# 006.net
KiCad netlist of a schematic drawn in EAGLE
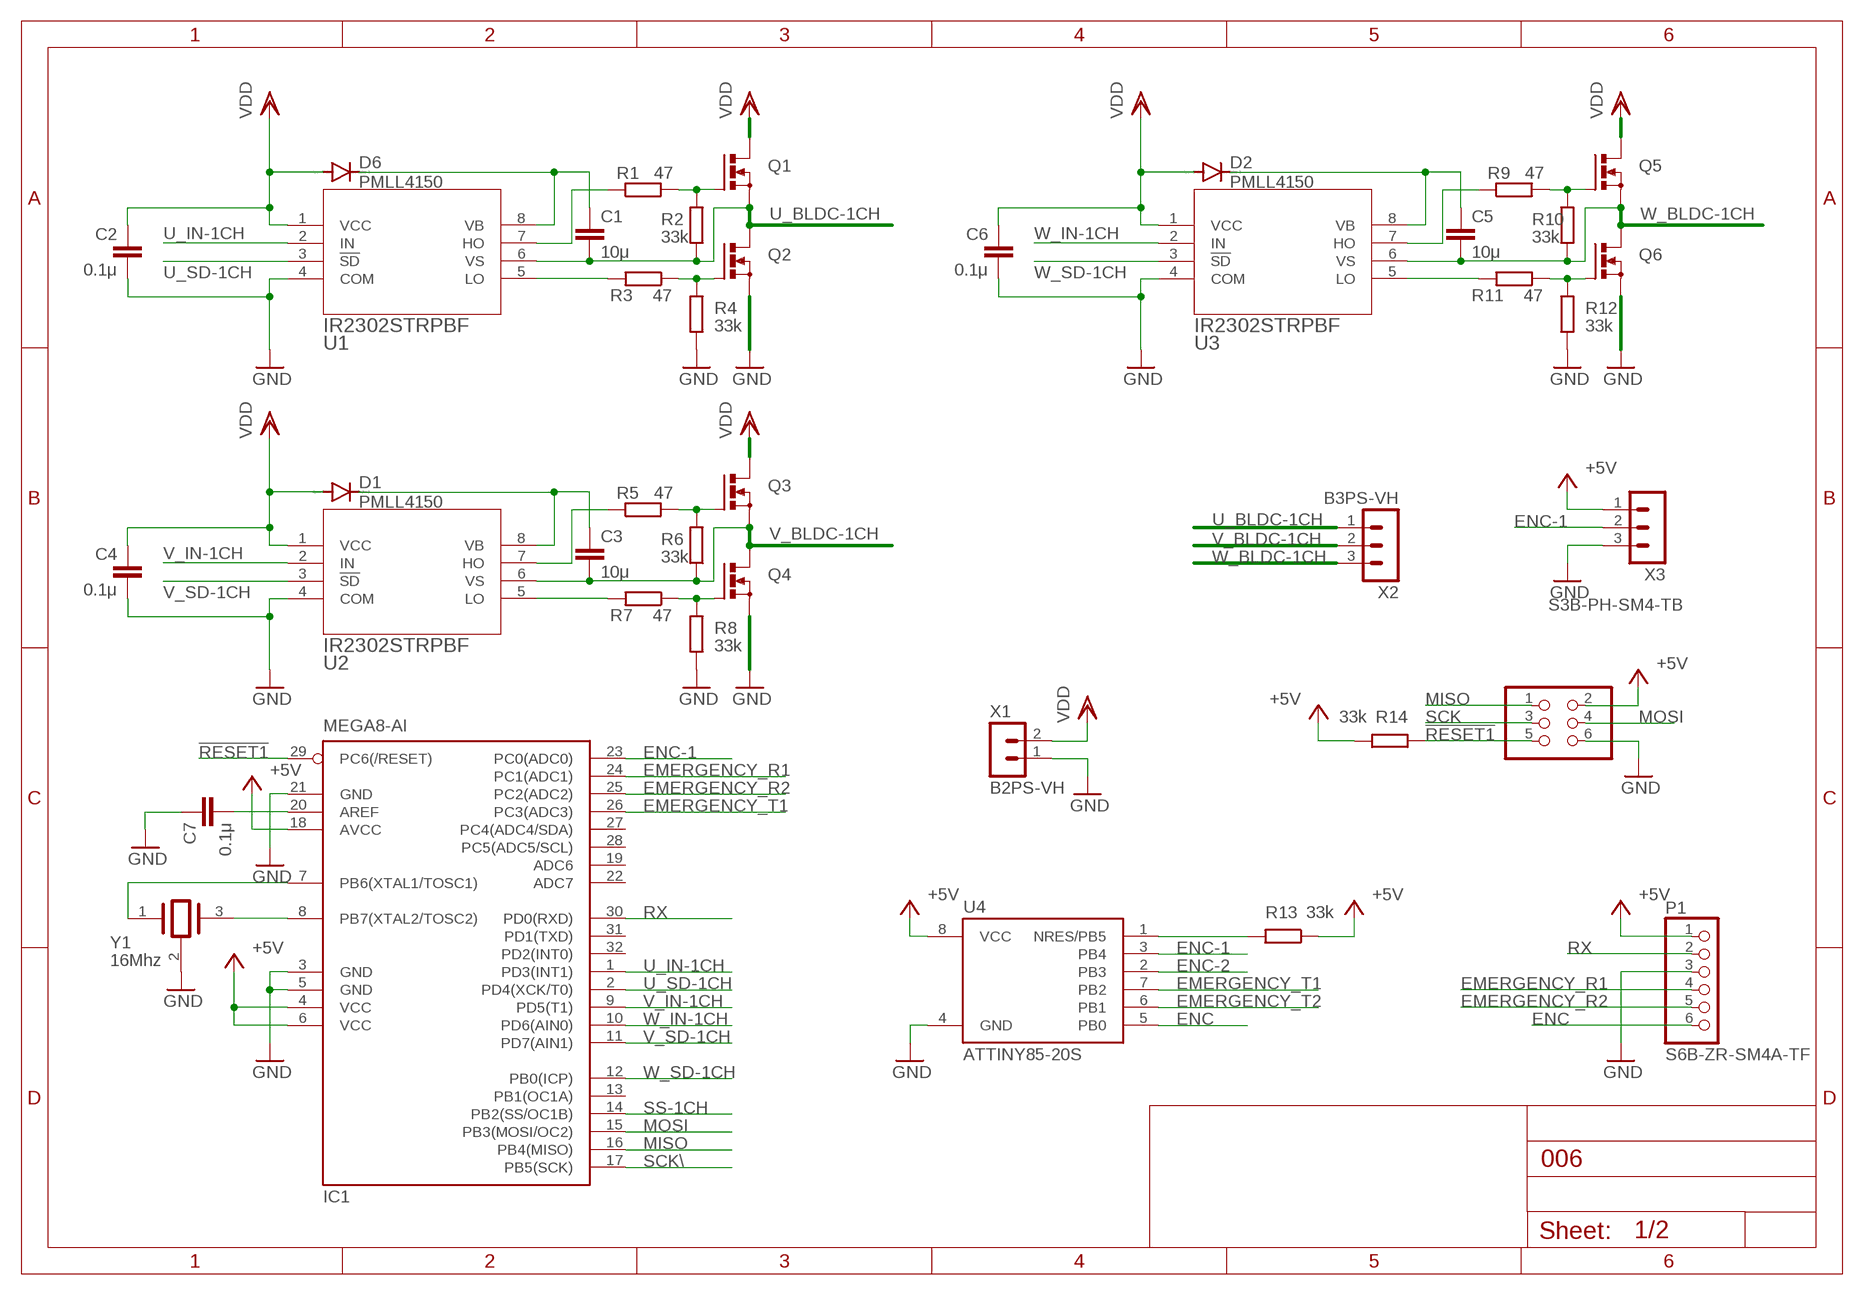
[diagram p0: schematic, sheet 1]
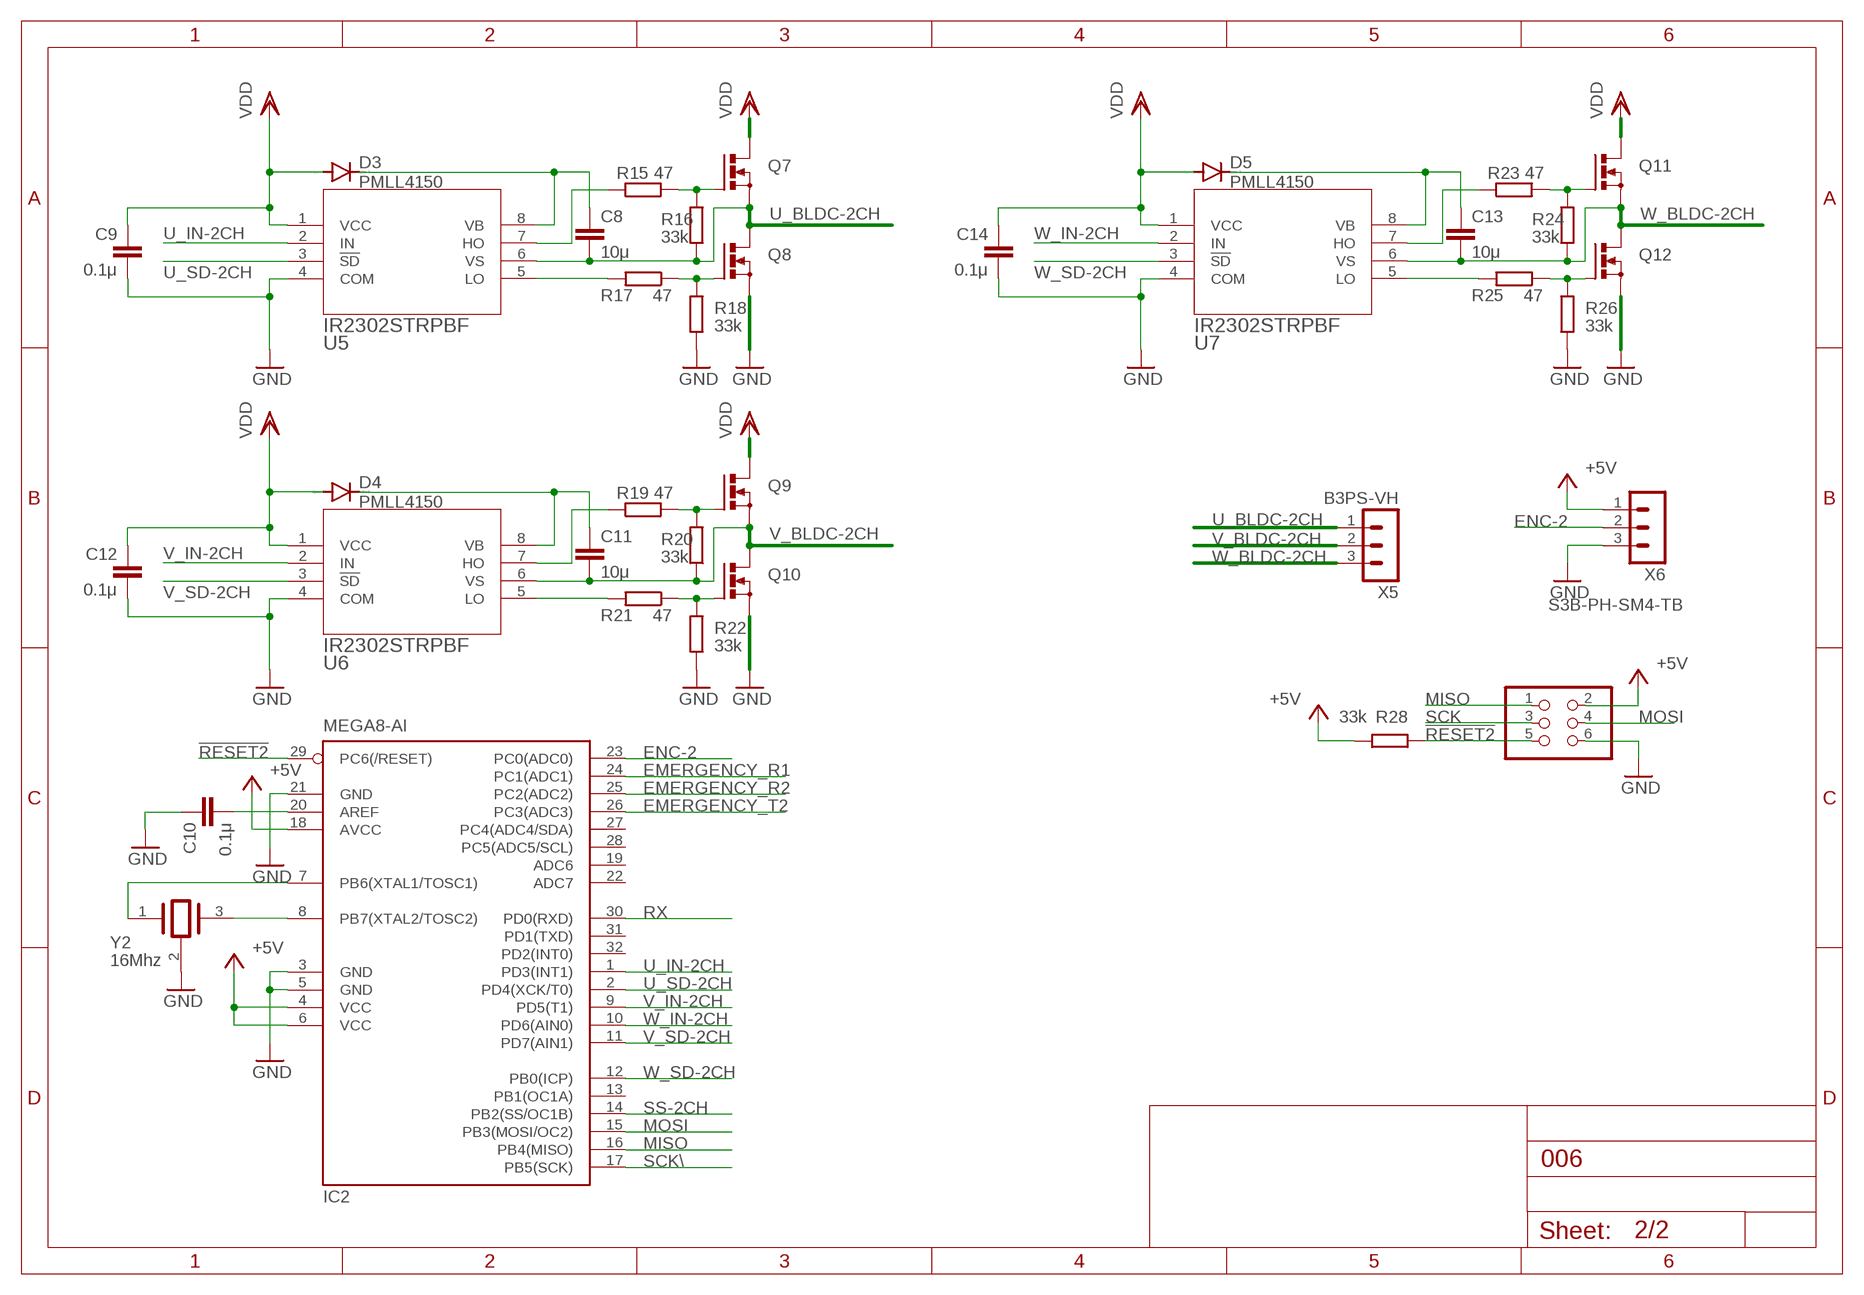
[diagram p1: schematic, sheet 2]

(export (version "E")
  (design (tool "Eeschema 10.0.6"))
  (components
    (comp (ref "C8")
      (value "10μ")
      (footprint "eagle-import:C1608")
      (libsource (lib "eagle-import") (part "C-EUC1608"))
    )
    (comp (ref "C9")
      (value "0.1μ")
      (footprint "eagle-import:C1608")
      (libsource (lib "eagle-import") (part "C-EUC1608"))
    )
    (comp (ref "C10")
      (value "0.1μ")
      (footprint "eagle-import:C1608")
      (libsource (lib "eagle-import") (part "C-EUC1608"))
    )
    (comp (ref "C11")
      (value "10μ")
      (footprint "eagle-import:C1608")
      (libsource (lib "eagle-import") (part "C-EUC1608"))
    )
    (comp (ref "C12")
      (value "0.1μ")
      (footprint "eagle-import:C1608")
      (libsource (lib "eagle-import") (part "C-EUC1608"))
    )
    (comp (ref "C13")
      (value "10μ")
      (footprint "eagle-import:C1608")
      (libsource (lib "eagle-import") (part "C-EUC1608"))
    )
    (comp (ref "C14")
      (value "0.1μ")
      (footprint "eagle-import:C1608")
      (libsource (lib "eagle-import") (part "C-EUC1608"))
    )
    (comp (ref "D3")
      (value "PMLL4150")
      (footprint "eagle-import:SOD80C")
      (libsource (lib "eagle-import") (part "PMLL4150"))
    )
    (comp (ref "D4")
      (value "PMLL4150")
      (footprint "eagle-import:SOD80C")
      (libsource (lib "eagle-import") (part "PMLL4150"))
    )
    (comp (ref "D5")
      (value "PMLL4150")
      (footprint "eagle-import:SOD80C")
      (libsource (lib "eagle-import") (part "PMLL4150"))
    )
    (comp (ref "IC2")
      (value "MEGA8-AI")
      (footprint "eagle-import:TQFP32-08")
      (fields (field (name "MPN") "ATMEGA8-16AU"))
      (libsource (lib "eagle-import") (part "MEGA8-AI"))
    )
    (comp (ref "JP2")
      (value "PINHD-2X3")
      (footprint "eagle-import:2X03")
      (libsource (lib "eagle-import") (part "PINHD-2X3"))
    )
    (comp (ref "Q7")
      (value "N-MOSFET-SO8S")
      (footprint "eagle-import:SO-08")
      (libsource (lib "eagle-import") (part "N-MOSFET-SO8S"))
    )
    (comp (ref "Q8")
      (value "N-MOSFET-SO8S")
      (footprint "eagle-import:SO-08")
      (libsource (lib "eagle-import") (part "N-MOSFET-SO8S"))
    )
    (comp (ref "Q9")
      (value "N-MOSFET-SO8S")
      (footprint "eagle-import:SO-08")
      (libsource (lib "eagle-import") (part "N-MOSFET-SO8S"))
    )
    (comp (ref "Q10")
      (value "N-MOSFET-SO8S")
      (footprint "eagle-import:SO-08")
      (libsource (lib "eagle-import") (part "N-MOSFET-SO8S"))
    )
    (comp (ref "Q11")
      (value "N-MOSFET-SO8S")
      (footprint "eagle-import:SO-08")
      (libsource (lib "eagle-import") (part "N-MOSFET-SO8S"))
    )
    (comp (ref "Q12")
      (value "N-MOSFET-SO8S")
      (footprint "eagle-import:SO-08")
      (libsource (lib "eagle-import") (part "N-MOSFET-SO8S"))
    )
    (comp (ref "R15")
      (value "47")
      (footprint "eagle-import:R0603")
      (libsource (lib "eagle-import") (part "R-EU_R0603"))
    )
    (comp (ref "R16")
      (value "33k")
      (footprint "eagle-import:R0603")
      (libsource (lib "eagle-import") (part "R-EU_R0603"))
    )
    (comp (ref "R17")
      (value "47")
      (footprint "eagle-import:R0603")
      (libsource (lib "eagle-import") (part "R-EU_R0603"))
    )
    (comp (ref "R18")
      (value "33k")
      (footprint "eagle-import:R0603")
      (libsource (lib "eagle-import") (part "R-EU_R0603"))
    )
    (comp (ref "R19")
      (value "47")
      (footprint "eagle-import:R0603")
      (libsource (lib "eagle-import") (part "R-EU_R0603"))
    )
    (comp (ref "R20")
      (value "33k")
      (footprint "eagle-import:R0603")
      (libsource (lib "eagle-import") (part "R-EU_R0603"))
    )
    (comp (ref "R21")
      (value "47")
      (footprint "eagle-import:R0603")
      (libsource (lib "eagle-import") (part "R-EU_R0603"))
    )
    (comp (ref "R22")
      (value "33k")
      (footprint "eagle-import:R0603")
      (libsource (lib "eagle-import") (part "R-EU_R0603"))
    )
    (comp (ref "R23")
      (value "47")
      (footprint "eagle-import:R0603")
      (libsource (lib "eagle-import") (part "R-EU_R0603"))
    )
    (comp (ref "R24")
      (value "33k")
      (footprint "eagle-import:R0603")
      (libsource (lib "eagle-import") (part "R-EU_R0603"))
    )
    (comp (ref "R25")
      (value "47")
      (footprint "eagle-import:R0603")
      (libsource (lib "eagle-import") (part "R-EU_R0603"))
    )
    (comp (ref "R26")
      (value "33k")
      (footprint "eagle-import:R0603")
      (libsource (lib "eagle-import") (part "R-EU_R0603"))
    )
    (comp (ref "R28")
      (value "33k")
      (footprint "eagle-import:R0603")
      (libsource (lib "eagle-import") (part "R-EU_R0603"))
    )
    (comp (ref "U5")
      (value "IR2302STRPBF")
      (footprint "eagle-import:PG-DSO-8-910_INF")
      (fields (field (name "COPYRIGHT") "Copyright (C) 2018 Accelerated Designs. All rights reserved"))
      (libsource (lib "eagle-import") (part "IR2302STRPBF"))
    )
    (comp (ref "U6")
      (value "IR2302STRPBF")
      (footprint "eagle-import:PG-DSO-8-910_INF")
      (fields (field (name "COPYRIGHT") "Copyright (C) 2018 Accelerated Designs. All rights reserved"))
      (libsource (lib "eagle-import") (part "IR2302STRPBF"))
    )
    (comp (ref "U7")
      (value "IR2302STRPBF")
      (footprint "eagle-import:PG-DSO-8-910_INF")
      (fields (field (name "COPYRIGHT") "Copyright (C) 2018 Accelerated Designs. All rights reserved"))
      (libsource (lib "eagle-import") (part "IR2302STRPBF"))
    )
    (comp (ref "X5")
      (value "B3PS-VH")
      (footprint "eagle-import:B3PS-VH")
      (libsource (lib "eagle-import") (part "B3PS-VH"))
    )
    (comp (ref "X6")
      (value "S3B-PH-SM4-TB")
      (footprint "eagle-import:S3B-PH-SM4-TB")
      (libsource (lib "eagle-import") (part "S3B-PH-SM4-TB"))
    )
    (comp (ref "Y2")
      (value "16Mhz")
      (footprint "eagle-import:MURATA_CSTNE16M0V53C000R0_0")
      (fields
        (field (name "DIGIKEY_PART_NUMBER") "490-17949-1-ND")
        (field (name "MF") "Murata")
        (field (name "MOUSER_PART_NUMBER") "81-CSTNE16M0V53C000R")
      )
      (libsource (lib "eagle-import") (part "MURATA_CSTNE16M0V53C000R0MURATA_CSTNE16M0V53C000R0_0_0"))
    )
    (comp (ref "C1")
      (value "10μ")
      (footprint "eagle-import:C1608")
      (libsource (lib "eagle-import") (part "C-EUC1608"))
    )
    (comp (ref "C2")
      (value "0.1μ")
      (footprint "eagle-import:C1608")
      (libsource (lib "eagle-import") (part "C-EUC1608"))
    )
    (comp (ref "C3")
      (value "10μ")
      (footprint "eagle-import:C1608")
      (libsource (lib "eagle-import") (part "C-EUC1608"))
    )
    (comp (ref "C4")
      (value "0.1μ")
      (footprint "eagle-import:C1608")
      (libsource (lib "eagle-import") (part "C-EUC1608"))
    )
    (comp (ref "C5")
      (value "10μ")
      (footprint "eagle-import:C1608")
      (libsource (lib "eagle-import") (part "C-EUC1608"))
    )
    (comp (ref "C6")
      (value "0.1μ")
      (footprint "eagle-import:C1608")
      (libsource (lib "eagle-import") (part "C-EUC1608"))
    )
    (comp (ref "C7")
      (value "0.1μ")
      (footprint "eagle-import:C1608")
      (libsource (lib "eagle-import") (part "C-EUC1608"))
    )
    (comp (ref "D1")
      (value "PMLL4150")
      (footprint "eagle-import:SOD80C")
      (libsource (lib "eagle-import") (part "PMLL4150"))
    )
    (comp (ref "D2")
      (value "PMLL4150")
      (footprint "eagle-import:SOD80C")
      (libsource (lib "eagle-import") (part "PMLL4150"))
    )
    (comp (ref "D6")
      (value "PMLL4150")
      (footprint "eagle-import:SOD80C")
      (libsource (lib "eagle-import") (part "PMLL4150"))
    )
    (comp (ref "IC1")
      (value "MEGA8-AI")
      (footprint "eagle-import:TQFP32-08")
      (fields (field (name "MPN") "ATMEGA8-16AU"))
      (libsource (lib "eagle-import") (part "MEGA8-AI"))
    )
    (comp (ref "JP1")
      (value "PINHD-2X3")
      (footprint "eagle-import:2X03")
      (libsource (lib "eagle-import") (part "PINHD-2X3"))
    )
    (comp (ref "P1")
      (value "S6B-ZR-SM4A-TF")
      (footprint "eagle-import:ZH-SM4-SIDE06")
      (libsource (lib "eagle-import") (part "S6B-ZR-SM4A-TF"))
    )
    (comp (ref "Q1")
      (value "N-MOSFET-SO8S")
      (footprint "eagle-import:SO-08")
      (libsource (lib "eagle-import") (part "N-MOSFET-SO8S"))
    )
    (comp (ref "Q2")
      (value "N-MOSFET-SO8S")
      (footprint "eagle-import:SO-08")
      (libsource (lib "eagle-import") (part "N-MOSFET-SO8S"))
    )
    (comp (ref "Q3")
      (value "N-MOSFET-SO8S")
      (footprint "eagle-import:SO-08")
      (libsource (lib "eagle-import") (part "N-MOSFET-SO8S"))
    )
    (comp (ref "Q4")
      (value "N-MOSFET-SO8S")
      (footprint "eagle-import:SO-08")
      (libsource (lib "eagle-import") (part "N-MOSFET-SO8S"))
    )
    (comp (ref "Q5")
      (value "N-MOSFET-SO8S")
      (footprint "eagle-import:SO-08")
      (libsource (lib "eagle-import") (part "N-MOSFET-SO8S"))
    )
    (comp (ref "Q6")
      (value "N-MOSFET-SO8S")
      (footprint "eagle-import:SO-08")
      (libsource (lib "eagle-import") (part "N-MOSFET-SO8S"))
    )
    (comp (ref "R1")
      (value "47")
      (footprint "eagle-import:R0603")
      (libsource (lib "eagle-import") (part "R-EU_R0603"))
    )
    (comp (ref "R2")
      (value "33k")
      (footprint "eagle-import:R0603")
      (libsource (lib "eagle-import") (part "R-EU_R0603"))
    )
    (comp (ref "R3")
      (value "47")
      (footprint "eagle-import:R0603")
      (libsource (lib "eagle-import") (part "R-EU_R0603"))
    )
    (comp (ref "R4")
      (value "33k")
      (footprint "eagle-import:R0603")
      (libsource (lib "eagle-import") (part "R-EU_R0603"))
    )
    (comp (ref "R5")
      (value "47")
      (footprint "eagle-import:R0603")
      (libsource (lib "eagle-import") (part "R-EU_R0603"))
    )
    (comp (ref "R6")
      (value "33k")
      (footprint "eagle-import:R0603")
      (libsource (lib "eagle-import") (part "R-EU_R0603"))
    )
    (comp (ref "R7")
      (value "47")
      (footprint "eagle-import:R0603")
      (libsource (lib "eagle-import") (part "R-EU_R0603"))
    )
    (comp (ref "R8")
      (value "33k")
      (footprint "eagle-import:R0603")
      (libsource (lib "eagle-import") (part "R-EU_R0603"))
    )
    (comp (ref "R9")
      (value "47")
      (footprint "eagle-import:R0603")
      (libsource (lib "eagle-import") (part "R-EU_R0603"))
    )
    (comp (ref "R10")
      (value "33k")
      (footprint "eagle-import:R0603")
      (libsource (lib "eagle-import") (part "R-EU_R0603"))
    )
    (comp (ref "R11")
      (value "47")
      (footprint "eagle-import:R0603")
      (libsource (lib "eagle-import") (part "R-EU_R0603"))
    )
    (comp (ref "R12")
      (value "33k")
      (footprint "eagle-import:R0603")
      (libsource (lib "eagle-import") (part "R-EU_R0603"))
    )
    (comp (ref "R13")
      (value "33k")
      (footprint "eagle-import:R0603")
      (libsource (lib "eagle-import") (part "R-EU_R0603"))
    )
    (comp (ref "R14")
      (value "33k")
      (footprint "eagle-import:R0603")
      (libsource (lib "eagle-import") (part "R-EU_R0603"))
    )
    (comp (ref "U1")
      (value "IR2302STRPBF")
      (footprint "eagle-import:PG-DSO-8-910_INF")
      (fields (field (name "COPYRIGHT") "Copyright (C) 2018 Accelerated Designs. All rights reserved"))
      (libsource (lib "eagle-import") (part "IR2302STRPBF"))
    )
    (comp (ref "U2")
      (value "IR2302STRPBF")
      (footprint "eagle-import:PG-DSO-8-910_INF")
      (fields (field (name "COPYRIGHT") "Copyright (C) 2018 Accelerated Designs. All rights reserved"))
      (libsource (lib "eagle-import") (part "IR2302STRPBF"))
    )
    (comp (ref "U3")
      (value "IR2302STRPBF")
      (footprint "eagle-import:PG-DSO-8-910_INF")
      (fields (field (name "COPYRIGHT") "Copyright (C) 2018 Accelerated Designs. All rights reserved"))
      (libsource (lib "eagle-import") (part "IR2302STRPBF"))
    )
    (comp (ref "U4")
      (value "ATTINY85-20S")
      (footprint "eagle-import:SOIC8_EIAJ_208MIL")
      (libsource (lib "eagle-import") (part "ATTINY85S-20"))
    )
    (comp (ref "X1")
      (value "B2PS-VH")
      (footprint "eagle-import:B2PS-VH")
      (libsource (lib "eagle-import") (part "B2PS-VH"))
    )
    (comp (ref "X2")
      (value "B3PS-VH")
      (footprint "eagle-import:B3PS-VH")
      (libsource (lib "eagle-import") (part "B3PS-VH"))
    )
    (comp (ref "X3")
      (value "S3B-PH-SM4-TB")
      (footprint "eagle-import:S3B-PH-SM4-TB")
      (libsource (lib "eagle-import") (part "S3B-PH-SM4-TB"))
    )
    (comp (ref "Y1")
      (value "16Mhz")
      (footprint "eagle-import:MURATA_CSTNE16M0V53C000R0_0")
      (fields
        (field (name "DIGIKEY_PART_NUMBER") "490-17949-1-ND")
        (field (name "MF") "Murata")
        (field (name "MOUSER_PART_NUMBER") "81-CSTNE16M0V53C000R")
      )
      (libsource (lib "eagle-import") (part "MURATA_CSTNE16M0V53C000R0MURATA_CSTNE16M0V53C000R0_0_0"))
    )
  )
  (nets
    (net (code "1") (name "+5V") (class "Default")
      (node (ref "IC1") (pin "18") (pinfunction "AVCC_18") (pintype "power_in"))
      (node (ref "IC1") (pin "4") (pinfunction "VCC_4") (pintype "power_in"))
      (node (ref "IC1") (pin "6") (pinfunction "VCC_6") (pintype "power_in"))
      (node (ref "IC2") (pin "18") (pinfunction "AVCC_18") (pintype "power_in"))
      (node (ref "IC2") (pin "4") (pinfunction "VCC_4") (pintype "power_in"))
      (node (ref "IC2") (pin "6") (pinfunction "VCC_6") (pintype "power_in"))
      (node (ref "JP1") (pin "2") (pinfunction "2_2") (pintype "passive"))
      (node (ref "JP2") (pin "2") (pinfunction "2_2") (pintype "passive"))
      (node (ref "P1") (pin "1") (pinfunction "1_1") (pintype "passive"))
      (node (ref "R13") (pin "1") (pinfunction "1_1") (pintype "passive"))
      (node (ref "R14") (pin "1") (pinfunction "1_1") (pintype "passive"))
      (node (ref "R28") (pin "1") (pinfunction "1_1") (pintype "passive"))
      (node (ref "U4") (pin "8") (pinfunction "VCC_8") (pintype "power_in"))
      (node (ref "X3") (pin "1") (pinfunction "1_1") (pintype "passive"))
      (node (ref "X6") (pin "1") (pinfunction "1_1") (pintype "passive"))
    )
    (net (code "2") (name "EMERGENCY_R1") (class "Default")
      (node (ref "IC1") (pin "24") (pinfunction "PC1(ADC1)_24") (pintype "bidirectional"))
      (node (ref "IC2") (pin "24") (pinfunction "PC1(ADC1)_24") (pintype "bidirectional"))
      (node (ref "P1") (pin "4") (pinfunction "4_4") (pintype "passive"))
    )
    (net (code "3") (name "EMERGENCY_R2") (class "Default")
      (node (ref "IC1") (pin "25") (pinfunction "PC2(ADC2)_25") (pintype "bidirectional"))
      (node (ref "IC2") (pin "25") (pinfunction "PC2(ADC2)_25") (pintype "bidirectional"))
      (node (ref "P1") (pin "5") (pinfunction "5_5") (pintype "passive"))
    )
    (net (code "4") (name "EMERGENCY_T1") (class "Default")
      (node (ref "IC1") (pin "26") (pinfunction "PC3(ADC3)_26") (pintype "bidirectional"))
      (node (ref "U4") (pin "7") (pinfunction "PB2_7") (pintype "bidirectional"))
    )
    (net (code "5") (name "EMERGENCY_T2") (class "Default")
      (node (ref "IC2") (pin "26") (pinfunction "PC3(ADC3)_26") (pintype "bidirectional"))
      (node (ref "U4") (pin "6") (pinfunction "PB1_6") (pintype "bidirectional"))
    )
    (net (code "6") (name "ENC") (class "Default")
      (node (ref "P1") (pin "6") (pinfunction "6_6") (pintype "passive"))
      (node (ref "U4") (pin "5") (pinfunction "PB0_5") (pintype "bidirectional"))
    )
    (net (code "7") (name "ENC-1") (class "Default")
      (node (ref "IC1") (pin "23") (pinfunction "PC0(ADC0)_23") (pintype "bidirectional"))
      (node (ref "U4") (pin "3") (pinfunction "PB4_3") (pintype "bidirectional"))
      (node (ref "X3") (pin "2") (pinfunction "2_2") (pintype "passive"))
    )
    (net (code "8") (name "ENC-2") (class "Default")
      (node (ref "IC2") (pin "23") (pinfunction "PC0(ADC0)_23") (pintype "bidirectional"))
      (node (ref "U4") (pin "2") (pinfunction "PB3_2") (pintype "bidirectional"))
      (node (ref "X6") (pin "2") (pinfunction "2_2") (pintype "passive"))
    )
    (net (code "9") (name "GND") (class "Default")
      (node (ref "C10") (pin "2") (pinfunction "2_2") (pintype "passive"))
      (node (ref "C12") (pin "1") (pinfunction "1_1") (pintype "passive"))
      (node (ref "C14") (pin "1") (pinfunction "1_1") (pintype "passive"))
      (node (ref "C2") (pin "1") (pinfunction "1_1") (pintype "passive"))
      (node (ref "C4") (pin "1") (pinfunction "1_1") (pintype "passive"))
      (node (ref "C6") (pin "1") (pinfunction "1_1") (pintype "passive"))
      (node (ref "C7") (pin "2") (pinfunction "2_2") (pintype "passive"))
      (node (ref "C9") (pin "1") (pinfunction "1_1") (pintype "passive"))
      (node (ref "IC1") (pin "21") (pinfunction "GND_21") (pintype "power_in"))
      (node (ref "IC1") (pin "3") (pinfunction "GND_3") (pintype "power_in"))
      (node (ref "IC1") (pin "5") (pinfunction "GND_5") (pintype "power_in"))
      (node (ref "IC2") (pin "21") (pinfunction "GND_21") (pintype "power_in"))
      (node (ref "IC2") (pin "3") (pinfunction "GND_3") (pintype "power_in"))
      (node (ref "IC2") (pin "5") (pinfunction "GND_5") (pintype "power_in"))
      (node (ref "JP1") (pin "6") (pinfunction "6_6") (pintype "passive"))
      (node (ref "JP2") (pin "6") (pinfunction "6_6") (pintype "passive"))
      (node (ref "P1") (pin "3") (pinfunction "3_3") (pintype "passive"))
      (node (ref "Q10") (pin "1") (pinfunction "S_1") (pintype "passive"))
      (node (ref "Q10") (pin "2") (pinfunction "S_2") (pintype "passive"))
      (node (ref "Q10") (pin "3") (pinfunction "S_3") (pintype "passive"))
      (node (ref "Q12") (pin "1") (pinfunction "S_1") (pintype "passive"))
      (node (ref "Q12") (pin "2") (pinfunction "S_2") (pintype "passive"))
      (node (ref "Q12") (pin "3") (pinfunction "S_3") (pintype "passive"))
      (node (ref "Q2") (pin "1") (pinfunction "S_1") (pintype "passive"))
      (node (ref "Q2") (pin "2") (pinfunction "S_2") (pintype "passive"))
      (node (ref "Q2") (pin "3") (pinfunction "S_3") (pintype "passive"))
      (node (ref "Q4") (pin "1") (pinfunction "S_1") (pintype "passive"))
      (node (ref "Q4") (pin "2") (pinfunction "S_2") (pintype "passive"))
      (node (ref "Q4") (pin "3") (pinfunction "S_3") (pintype "passive"))
      (node (ref "Q6") (pin "1") (pinfunction "S_1") (pintype "passive"))
      (node (ref "Q6") (pin "2") (pinfunction "S_2") (pintype "passive"))
      (node (ref "Q6") (pin "3") (pinfunction "S_3") (pintype "passive"))
      (node (ref "Q8") (pin "1") (pinfunction "S_1") (pintype "passive"))
      (node (ref "Q8") (pin "2") (pinfunction "S_2") (pintype "passive"))
      (node (ref "Q8") (pin "3") (pinfunction "S_3") (pintype "passive"))
      (node (ref "R12") (pin "1") (pinfunction "1_1") (pintype "passive"))
      (node (ref "R18") (pin "1") (pinfunction "1_1") (pintype "passive"))
      (node (ref "R22") (pin "1") (pinfunction "1_1") (pintype "passive"))
      (node (ref "R26") (pin "1") (pinfunction "1_1") (pintype "passive"))
      (node (ref "R4") (pin "1") (pinfunction "1_1") (pintype "passive"))
      (node (ref "R8") (pin "1") (pinfunction "1_1") (pintype "passive"))
      (node (ref "U1") (pin "4") (pinfunction "COM_4") (pintype "passive"))
      (node (ref "U2") (pin "4") (pinfunction "COM_4") (pintype "passive"))
      (node (ref "U3") (pin "4") (pinfunction "COM_4") (pintype "passive"))
      (node (ref "U4") (pin "4") (pinfunction "GND_4") (pintype "power_in"))
      (node (ref "U5") (pin "4") (pinfunction "COM_4") (pintype "passive"))
      (node (ref "U6") (pin "4") (pinfunction "COM_4") (pintype "passive"))
      (node (ref "U7") (pin "4") (pinfunction "COM_4") (pintype "passive"))
      (node (ref "X1") (pin "1") (pinfunction "1_1") (pintype "passive"))
      (node (ref "X3") (pin "3") (pinfunction "3_3") (pintype "passive"))
      (node (ref "X6") (pin "3") (pinfunction "3_3") (pintype "passive"))
      (node (ref "Y1") (pin "2") (pinfunction "GND_2") (pintype "power_in"))
      (node (ref "Y2") (pin "2") (pinfunction "GND_2") (pintype "power_in"))
    )
    (net (code "10") (name "MISO") (class "Default")
      (node (ref "IC1") (pin "16") (pinfunction "PB4(MISO)_16") (pintype "bidirectional"))
      (node (ref "IC2") (pin "16") (pinfunction "PB4(MISO)_16") (pintype "bidirectional"))
      (node (ref "JP1") (pin "1") (pinfunction "1_1") (pintype "passive"))
      (node (ref "JP2") (pin "1") (pinfunction "1_1") (pintype "passive"))
    )
    (net (code "11") (name "MOSI") (class "Default")
      (node (ref "IC1") (pin "15") (pinfunction "PB3(MOSI/OC2)_15") (pintype "bidirectional"))
      (node (ref "IC2") (pin "15") (pinfunction "PB3(MOSI/OC2)_15") (pintype "bidirectional"))
      (node (ref "JP1") (pin "4") (pinfunction "4_4") (pintype "passive"))
      (node (ref "JP2") (pin "4") (pinfunction "4_4") (pintype "passive"))
    )
    (net (code "12") (name "Net-(IC1-AREF)") (class "Default")
      (node (ref "C7") (pin "1") (pinfunction "1_1") (pintype "passive"))
      (node (ref "IC1") (pin "20") (pinfunction "AREF_20") (pintype "passive"))
    )
    (net (code "13") (name "Net-(IC1-PB6(XTAL1{slash}TOSC1))") (class "Default")
      (node (ref "IC1") (pin "7") (pinfunction "PB6(XTAL1/TOSC1)_7") (pintype "bidirectional"))
      (node (ref "Y1") (pin "1") (pinfunction "INPUT_1") (pintype "input"))
    )
    (net (code "14") (name "Net-(IC1-PB7(XTAL2{slash}TOSC2))") (class "Default")
      (node (ref "IC1") (pin "8") (pinfunction "PB7(XTAL2/TOSC2)_8") (pintype "bidirectional"))
      (node (ref "Y1") (pin "3") (pinfunction "OUTPUT_3") (pintype "output"))
    )
    (net (code "15") (name "Net-(IC2-AREF)") (class "Default")
      (node (ref "C10") (pin "1") (pinfunction "1_1") (pintype "passive"))
      (node (ref "IC2") (pin "20") (pinfunction "AREF_20") (pintype "passive"))
    )
    (net (code "16") (name "Net-(IC2-PB6(XTAL1{slash}TOSC1))") (class "Default")
      (node (ref "IC2") (pin "7") (pinfunction "PB6(XTAL1/TOSC1)_7") (pintype "bidirectional"))
      (node (ref "Y2") (pin "1") (pinfunction "INPUT_1") (pintype "input"))
    )
    (net (code "17") (name "Net-(IC2-PB7(XTAL2{slash}TOSC2))") (class "Default")
      (node (ref "IC2") (pin "8") (pinfunction "PB7(XTAL2/TOSC2)_8") (pintype "bidirectional"))
      (node (ref "Y2") (pin "3") (pinfunction "OUTPUT_3") (pintype "output"))
    )
    (net (code "18") (name "Net-(Q1-G)") (class "Default")
      (node (ref "Q1") (pin "4") (pinfunction "G_4") (pintype "passive"))
      (node (ref "R1") (pin "2") (pinfunction "2_2") (pintype "passive"))
      (node (ref "R2") (pin "2") (pinfunction "2_2") (pintype "passive"))
    )
    (net (code "19") (name "Net-(Q2-G)") (class "Default")
      (node (ref "Q2") (pin "4") (pinfunction "G_4") (pintype "passive"))
      (node (ref "R3") (pin "1") (pinfunction "1_1") (pintype "passive"))
      (node (ref "R4") (pin "2") (pinfunction "2_2") (pintype "passive"))
    )
    (net (code "20") (name "Net-(Q3-G)") (class "Default")
      (node (ref "Q3") (pin "4") (pinfunction "G_4") (pintype "passive"))
      (node (ref "R5") (pin "2") (pinfunction "2_2") (pintype "passive"))
      (node (ref "R6") (pin "2") (pinfunction "2_2") (pintype "passive"))
    )
    (net (code "21") (name "Net-(Q4-G)") (class "Default")
      (node (ref "Q4") (pin "4") (pinfunction "G_4") (pintype "passive"))
      (node (ref "R7") (pin "1") (pinfunction "1_1") (pintype "passive"))
      (node (ref "R8") (pin "2") (pinfunction "2_2") (pintype "passive"))
    )
    (net (code "22") (name "Net-(Q5-G)") (class "Default")
      (node (ref "Q5") (pin "4") (pinfunction "G_4") (pintype "passive"))
      (node (ref "R10") (pin "2") (pinfunction "2_2") (pintype "passive"))
      (node (ref "R9") (pin "2") (pinfunction "2_2") (pintype "passive"))
    )
    (net (code "23") (name "Net-(Q6-G)") (class "Default")
      (node (ref "Q6") (pin "4") (pinfunction "G_4") (pintype "passive"))
      (node (ref "R11") (pin "1") (pinfunction "1_1") (pintype "passive"))
      (node (ref "R12") (pin "2") (pinfunction "2_2") (pintype "passive"))
    )
    (net (code "24") (name "Net-(Q7-G)") (class "Default")
      (node (ref "Q7") (pin "4") (pinfunction "G_4") (pintype "passive"))
      (node (ref "R15") (pin "2") (pinfunction "2_2") (pintype "passive"))
      (node (ref "R16") (pin "2") (pinfunction "2_2") (pintype "passive"))
    )
    (net (code "25") (name "Net-(Q8-G)") (class "Default")
      (node (ref "Q8") (pin "4") (pinfunction "G_4") (pintype "passive"))
      (node (ref "R17") (pin "1") (pinfunction "1_1") (pintype "passive"))
      (node (ref "R18") (pin "2") (pinfunction "2_2") (pintype "passive"))
    )
    (net (code "26") (name "Net-(Q9-G)") (class "Default")
      (node (ref "Q9") (pin "4") (pinfunction "G_4") (pintype "passive"))
      (node (ref "R19") (pin "2") (pinfunction "2_2") (pintype "passive"))
      (node (ref "R20") (pin "2") (pinfunction "2_2") (pintype "passive"))
    )
    (net (code "27") (name "Net-(Q10-G)") (class "Default")
      (node (ref "Q10") (pin "4") (pinfunction "G_4") (pintype "passive"))
      (node (ref "R21") (pin "1") (pinfunction "1_1") (pintype "passive"))
      (node (ref "R22") (pin "2") (pinfunction "2_2") (pintype "passive"))
    )
    (net (code "28") (name "Net-(Q11-G)") (class "Default")
      (node (ref "Q11") (pin "4") (pinfunction "G_4") (pintype "passive"))
      (node (ref "R23") (pin "2") (pinfunction "2_2") (pintype "passive"))
      (node (ref "R24") (pin "2") (pinfunction "2_2") (pintype "passive"))
    )
    (net (code "29") (name "Net-(Q12-G)") (class "Default")
      (node (ref "Q12") (pin "4") (pinfunction "G_4") (pintype "passive"))
      (node (ref "R25") (pin "1") (pinfunction "1_1") (pintype "passive"))
      (node (ref "R26") (pin "2") (pinfunction "2_2") (pintype "passive"))
    )
    (net (code "30") (name "Net-(U1-HO)") (class "Default")
      (node (ref "R1") (pin "1") (pinfunction "1_1") (pintype "passive"))
      (node (ref "U1") (pin "7") (pinfunction "HO_7") (pintype "output"))
    )
    (net (code "31") (name "Net-(U1-LO)") (class "Default")
      (node (ref "R3") (pin "2") (pinfunction "2_2") (pintype "passive"))
      (node (ref "U1") (pin "5") (pinfunction "LO_5") (pintype "output"))
    )
    (net (code "32") (name "Net-(U1-VB)") (class "Default")
      (node (ref "C1") (pin "1") (pinfunction "1_1") (pintype "passive"))
      (node (ref "D6") (pin "C") (pinfunction "C_C") (pintype "passive"))
      (node (ref "U1") (pin "8") (pinfunction "VB_8") (pintype "power_in"))
    )
    (net (code "33") (name "Net-(U2-HO)") (class "Default")
      (node (ref "R5") (pin "1") (pinfunction "1_1") (pintype "passive"))
      (node (ref "U2") (pin "7") (pinfunction "HO_7") (pintype "output"))
    )
    (net (code "34") (name "Net-(U2-LO)") (class "Default")
      (node (ref "R7") (pin "2") (pinfunction "2_2") (pintype "passive"))
      (node (ref "U2") (pin "5") (pinfunction "LO_5") (pintype "output"))
    )
    (net (code "35") (name "Net-(U2-VB)") (class "Default")
      (node (ref "C3") (pin "1") (pinfunction "1_1") (pintype "passive"))
      (node (ref "D1") (pin "C") (pinfunction "C_C") (pintype "passive"))
      (node (ref "U2") (pin "8") (pinfunction "VB_8") (pintype "power_in"))
    )
    (net (code "36") (name "Net-(U3-HO)") (class "Default")
      (node (ref "R9") (pin "1") (pinfunction "1_1") (pintype "passive"))
      (node (ref "U3") (pin "7") (pinfunction "HO_7") (pintype "output"))
    )
    (net (code "37") (name "Net-(U3-LO)") (class "Default")
      (node (ref "R11") (pin "2") (pinfunction "2_2") (pintype "passive"))
      (node (ref "U3") (pin "5") (pinfunction "LO_5") (pintype "output"))
    )
    (net (code "38") (name "Net-(U3-VB)") (class "Default")
      (node (ref "C5") (pin "1") (pinfunction "1_1") (pintype "passive"))
      (node (ref "D2") (pin "C") (pinfunction "C_C") (pintype "passive"))
      (node (ref "U3") (pin "8") (pinfunction "VB_8") (pintype "power_in"))
    )
    (net (code "39") (name "Net-(U4-NRES{slash}PB5)") (class "Default")
      (node (ref "R13") (pin "2") (pinfunction "2_2") (pintype "passive"))
      (node (ref "U4") (pin "1") (pinfunction "NRES/PB5_1") (pintype "bidirectional"))
    )
    (net (code "40") (name "Net-(U5-HO)") (class "Default")
      (node (ref "R15") (pin "1") (pinfunction "1_1") (pintype "passive"))
      (node (ref "U5") (pin "7") (pinfunction "HO_7") (pintype "output"))
    )
    (net (code "41") (name "Net-(U5-LO)") (class "Default")
      (node (ref "R17") (pin "2") (pinfunction "2_2") (pintype "passive"))
      (node (ref "U5") (pin "5") (pinfunction "LO_5") (pintype "output"))
    )
    (net (code "42") (name "Net-(U5-VB)") (class "Default")
      (node (ref "C8") (pin "1") (pinfunction "1_1") (pintype "passive"))
      (node (ref "D3") (pin "C") (pinfunction "C_C") (pintype "passive"))
      (node (ref "U5") (pin "8") (pinfunction "VB_8") (pintype "power_in"))
    )
    (net (code "43") (name "Net-(U6-HO)") (class "Default")
      (node (ref "R19") (pin "1") (pinfunction "1_1") (pintype "passive"))
      (node (ref "U6") (pin "7") (pinfunction "HO_7") (pintype "output"))
    )
    (net (code "44") (name "Net-(U6-LO)") (class "Default")
      (node (ref "R21") (pin "2") (pinfunction "2_2") (pintype "passive"))
      (node (ref "U6") (pin "5") (pinfunction "LO_5") (pintype "output"))
    )
    (net (code "45") (name "Net-(U6-VB)") (class "Default")
      (node (ref "C11") (pin "1") (pinfunction "1_1") (pintype "passive"))
      (node (ref "D4") (pin "C") (pinfunction "C_C") (pintype "passive"))
      (node (ref "U6") (pin "8") (pinfunction "VB_8") (pintype "power_in"))
    )
    (net (code "46") (name "Net-(U7-HO)") (class "Default")
      (node (ref "R23") (pin "1") (pinfunction "1_1") (pintype "passive"))
      (node (ref "U7") (pin "7") (pinfunction "HO_7") (pintype "output"))
    )
    (net (code "47") (name "Net-(U7-LO)") (class "Default")
      (node (ref "R25") (pin "2") (pinfunction "2_2") (pintype "passive"))
      (node (ref "U7") (pin "5") (pinfunction "LO_5") (pintype "output"))
    )
    (net (code "48") (name "Net-(U7-VB)") (class "Default")
      (node (ref "C13") (pin "1") (pinfunction "1_1") (pintype "passive"))
      (node (ref "D5") (pin "C") (pinfunction "C_C") (pintype "passive"))
      (node (ref "U7") (pin "8") (pinfunction "VB_8") (pintype "power_in"))
    )
    (net (code "49") (name "RX") (class "Default")
      (node (ref "IC1") (pin "30") (pinfunction "PD0(RXD)_30") (pintype "bidirectional"))
      (node (ref "IC2") (pin "30") (pinfunction "PD0(RXD)_30") (pintype "bidirectional"))
      (node (ref "P1") (pin "2") (pinfunction "2_2") (pintype "passive"))
    )
    (net (code "50") (name "SCK") (class "Default")
      (node (ref "JP1") (pin "3") (pinfunction "3_3") (pintype "passive"))
      (node (ref "JP2") (pin "3") (pinfunction "3_3") (pintype "passive"))
    )
    (net (code "51") (name "SCK\\") (class "Default")
      (node (ref "IC1") (pin "17") (pinfunction "PB5(SCK)_17") (pintype "bidirectional"))
      (node (ref "IC2") (pin "17") (pinfunction "PB5(SCK)_17") (pintype "bidirectional"))
    )
    (net (code "52") (name "SS-1CH") (class "Default")
      (node (ref "IC1") (pin "14") (pinfunction "PB2(SS/OC1B)_14") (pintype "bidirectional"))
    )
    (net (code "53") (name "SS-2CH") (class "Default")
      (node (ref "IC2") (pin "14") (pinfunction "PB2(SS/OC1B)_14") (pintype "bidirectional"))
    )
    (net (code "54") (name "U_BLDC-1CH") (class "Default")
      (node (ref "C1") (pin "2") (pinfunction "2_2") (pintype "passive"))
      (node (ref "Q1") (pin "1") (pinfunction "S_1") (pintype "passive"))
      (node (ref "Q1") (pin "2") (pinfunction "S_2") (pintype "passive"))
      (node (ref "Q1") (pin "3") (pinfunction "S_3") (pintype "passive"))
      (node (ref "Q2") (pin "5") (pinfunction "D_5") (pintype "passive"))
      (node (ref "Q2") (pin "6") (pinfunction "D_6") (pintype "passive"))
      (node (ref "Q2") (pin "7") (pinfunction "D_7") (pintype "passive"))
      (node (ref "Q2") (pin "8") (pinfunction "D_8") (pintype "passive"))
      (node (ref "R2") (pin "1") (pinfunction "1_1") (pintype "passive"))
      (node (ref "U1") (pin "6") (pinfunction "VS_6") (pintype "power_in"))
      (node (ref "X2") (pin "1") (pinfunction "1_1") (pintype "passive"))
    )
    (net (code "55") (name "U_BLDC-2CH") (class "Default")
      (node (ref "C8") (pin "2") (pinfunction "2_2") (pintype "passive"))
      (node (ref "Q7") (pin "1") (pinfunction "S_1") (pintype "passive"))
      (node (ref "Q7") (pin "2") (pinfunction "S_2") (pintype "passive"))
      (node (ref "Q7") (pin "3") (pinfunction "S_3") (pintype "passive"))
      (node (ref "Q8") (pin "5") (pinfunction "D_5") (pintype "passive"))
      (node (ref "Q8") (pin "6") (pinfunction "D_6") (pintype "passive"))
      (node (ref "Q8") (pin "7") (pinfunction "D_7") (pintype "passive"))
      (node (ref "Q8") (pin "8") (pinfunction "D_8") (pintype "passive"))
      (node (ref "R16") (pin "1") (pinfunction "1_1") (pintype "passive"))
      (node (ref "U5") (pin "6") (pinfunction "VS_6") (pintype "power_in"))
      (node (ref "X5") (pin "1") (pinfunction "1_1") (pintype "passive"))
    )
    (net (code "56") (name "U_IN-1CH") (class "Default")
      (node (ref "IC1") (pin "1") (pinfunction "PD3(INT1)_1") (pintype "bidirectional"))
      (node (ref "U1") (pin "2") (pinfunction "IN_2") (pintype "input"))
    )
    (net (code "57") (name "U_IN-2CH") (class "Default")
      (node (ref "IC2") (pin "1") (pinfunction "PD3(INT1)_1") (pintype "bidirectional"))
      (node (ref "U5") (pin "2") (pinfunction "IN_2") (pintype "input"))
    )
    (net (code "58") (name "U_SD-1CH") (class "Default")
      (node (ref "IC1") (pin "2") (pinfunction "PD4(XCK/T0)_2") (pintype "bidirectional"))
      (node (ref "U1") (pin "3") (pinfunction "~{SD}_3") (pintype "input"))
    )
    (net (code "59") (name "U_SD-2CH") (class "Default")
      (node (ref "IC2") (pin "2") (pinfunction "PD4(XCK/T0)_2") (pintype "bidirectional"))
      (node (ref "U5") (pin "3") (pinfunction "~{SD}_3") (pintype "input"))
    )
    (net (code "60") (name "VDD") (class "Default")
      (node (ref "C12") (pin "2") (pinfunction "2_2") (pintype "passive"))
      (node (ref "C14") (pin "2") (pinfunction "2_2") (pintype "passive"))
      (node (ref "C2") (pin "2") (pinfunction "2_2") (pintype "passive"))
      (node (ref "C4") (pin "2") (pinfunction "2_2") (pintype "passive"))
      (node (ref "C6") (pin "2") (pinfunction "2_2") (pintype "passive"))
      (node (ref "C9") (pin "2") (pinfunction "2_2") (pintype "passive"))
      (node (ref "D1") (pin "A") (pinfunction "A_A") (pintype "passive"))
      (node (ref "D2") (pin "A") (pinfunction "A_A") (pintype "passive"))
      (node (ref "D3") (pin "A") (pinfunction "A_A") (pintype "passive"))
      (node (ref "D4") (pin "A") (pinfunction "A_A") (pintype "passive"))
      (node (ref "D5") (pin "A") (pinfunction "A_A") (pintype "passive"))
      (node (ref "D6") (pin "A") (pinfunction "A_A") (pintype "passive"))
      (node (ref "Q1") (pin "5") (pinfunction "D_5") (pintype "passive"))
      (node (ref "Q1") (pin "6") (pinfunction "D_6") (pintype "passive"))
      (node (ref "Q1") (pin "7") (pinfunction "D_7") (pintype "passive"))
      (node (ref "Q1") (pin "8") (pinfunction "D_8") (pintype "passive"))
      (node (ref "Q11") (pin "5") (pinfunction "D_5") (pintype "passive"))
      (node (ref "Q11") (pin "6") (pinfunction "D_6") (pintype "passive"))
      (node (ref "Q11") (pin "7") (pinfunction "D_7") (pintype "passive"))
      (node (ref "Q11") (pin "8") (pinfunction "D_8") (pintype "passive"))
      (node (ref "Q3") (pin "5") (pinfunction "D_5") (pintype "passive"))
      (node (ref "Q3") (pin "6") (pinfunction "D_6") (pintype "passive"))
      (node (ref "Q3") (pin "7") (pinfunction "D_7") (pintype "passive"))
      (node (ref "Q3") (pin "8") (pinfunction "D_8") (pintype "passive"))
      (node (ref "Q5") (pin "5") (pinfunction "D_5") (pintype "passive"))
      (node (ref "Q5") (pin "6") (pinfunction "D_6") (pintype "passive"))
      (node (ref "Q5") (pin "7") (pinfunction "D_7") (pintype "passive"))
      (node (ref "Q5") (pin "8") (pinfunction "D_8") (pintype "passive"))
      (node (ref "Q7") (pin "5") (pinfunction "D_5") (pintype "passive"))
      (node (ref "Q7") (pin "6") (pinfunction "D_6") (pintype "passive"))
      (node (ref "Q7") (pin "7") (pinfunction "D_7") (pintype "passive"))
      (node (ref "Q7") (pin "8") (pinfunction "D_8") (pintype "passive"))
      (node (ref "Q9") (pin "5") (pinfunction "D_5") (pintype "passive"))
      (node (ref "Q9") (pin "6") (pinfunction "D_6") (pintype "passive"))
      (node (ref "Q9") (pin "7") (pinfunction "D_7") (pintype "passive"))
      (node (ref "Q9") (pin "8") (pinfunction "D_8") (pintype "passive"))
      (node (ref "U1") (pin "1") (pinfunction "VCC_1") (pintype "power_in"))
      (node (ref "U2") (pin "1") (pinfunction "VCC_1") (pintype "power_in"))
      (node (ref "U3") (pin "1") (pinfunction "VCC_1") (pintype "power_in"))
      (node (ref "U5") (pin "1") (pinfunction "VCC_1") (pintype "power_in"))
      (node (ref "U6") (pin "1") (pinfunction "VCC_1") (pintype "power_in"))
      (node (ref "U7") (pin "1") (pinfunction "VCC_1") (pintype "power_in"))
      (node (ref "X1") (pin "2") (pinfunction "2_2") (pintype "passive"))
    )
    (net (code "61") (name "V_BLDC-1CH") (class "Default")
      (node (ref "C3") (pin "2") (pinfunction "2_2") (pintype "passive"))
      (node (ref "Q3") (pin "1") (pinfunction "S_1") (pintype "passive"))
      (node (ref "Q3") (pin "2") (pinfunction "S_2") (pintype "passive"))
      (node (ref "Q3") (pin "3") (pinfunction "S_3") (pintype "passive"))
      (node (ref "Q4") (pin "5") (pinfunction "D_5") (pintype "passive"))
      (node (ref "Q4") (pin "6") (pinfunction "D_6") (pintype "passive"))
      (node (ref "Q4") (pin "7") (pinfunction "D_7") (pintype "passive"))
      (node (ref "Q4") (pin "8") (pinfunction "D_8") (pintype "passive"))
      (node (ref "R6") (pin "1") (pinfunction "1_1") (pintype "passive"))
      (node (ref "U2") (pin "6") (pinfunction "VS_6") (pintype "power_in"))
      (node (ref "X2") (pin "2") (pinfunction "2_2") (pintype "passive"))
    )
    (net (code "62") (name "V_BLDC-2CH") (class "Default")
      (node (ref "C11") (pin "2") (pinfunction "2_2") (pintype "passive"))
      (node (ref "Q10") (pin "5") (pinfunction "D_5") (pintype "passive"))
      (node (ref "Q10") (pin "6") (pinfunction "D_6") (pintype "passive"))
      (node (ref "Q10") (pin "7") (pinfunction "D_7") (pintype "passive"))
      (node (ref "Q10") (pin "8") (pinfunction "D_8") (pintype "passive"))
      (node (ref "Q9") (pin "1") (pinfunction "S_1") (pintype "passive"))
      (node (ref "Q9") (pin "2") (pinfunction "S_2") (pintype "passive"))
      (node (ref "Q9") (pin "3") (pinfunction "S_3") (pintype "passive"))
      (node (ref "R20") (pin "1") (pinfunction "1_1") (pintype "passive"))
      (node (ref "U6") (pin "6") (pinfunction "VS_6") (pintype "power_in"))
      (node (ref "X5") (pin "2") (pinfunction "2_2") (pintype "passive"))
    )
    (net (code "63") (name "V_IN-1CH") (class "Default")
      (node (ref "IC1") (pin "9") (pinfunction "PD5(T1)_9") (pintype "bidirectional"))
      (node (ref "U2") (pin "2") (pinfunction "IN_2") (pintype "input"))
    )
    (net (code "64") (name "V_IN-2CH") (class "Default")
      (node (ref "IC2") (pin "9") (pinfunction "PD5(T1)_9") (pintype "bidirectional"))
      (node (ref "U6") (pin "2") (pinfunction "IN_2") (pintype "input"))
    )
    (net (code "65") (name "V_SD-1CH") (class "Default")
      (node (ref "IC1") (pin "11") (pinfunction "PD7(AIN1)_11") (pintype "bidirectional"))
      (node (ref "U2") (pin "3") (pinfunction "~{SD}_3") (pintype "input"))
    )
    (net (code "66") (name "V_SD-2CH") (class "Default")
      (node (ref "IC2") (pin "11") (pinfunction "PD7(AIN1)_11") (pintype "bidirectional"))
      (node (ref "U6") (pin "3") (pinfunction "~{SD}_3") (pintype "input"))
    )
    (net (code "67") (name "W_BLDC-1CH") (class "Default")
      (node (ref "C5") (pin "2") (pinfunction "2_2") (pintype "passive"))
      (node (ref "Q5") (pin "1") (pinfunction "S_1") (pintype "passive"))
      (node (ref "Q5") (pin "2") (pinfunction "S_2") (pintype "passive"))
      (node (ref "Q5") (pin "3") (pinfunction "S_3") (pintype "passive"))
      (node (ref "Q6") (pin "5") (pinfunction "D_5") (pintype "passive"))
      (node (ref "Q6") (pin "6") (pinfunction "D_6") (pintype "passive"))
      (node (ref "Q6") (pin "7") (pinfunction "D_7") (pintype "passive"))
      (node (ref "Q6") (pin "8") (pinfunction "D_8") (pintype "passive"))
      (node (ref "R10") (pin "1") (pinfunction "1_1") (pintype "passive"))
      (node (ref "U3") (pin "6") (pinfunction "VS_6") (pintype "power_in"))
      (node (ref "X2") (pin "3") (pinfunction "3_3") (pintype "passive"))
    )
    (net (code "68") (name "W_BLDC-2CH") (class "Default")
      (node (ref "C13") (pin "2") (pinfunction "2_2") (pintype "passive"))
      (node (ref "Q11") (pin "1") (pinfunction "S_1") (pintype "passive"))
      (node (ref "Q11") (pin "2") (pinfunction "S_2") (pintype "passive"))
      (node (ref "Q11") (pin "3") (pinfunction "S_3") (pintype "passive"))
      (node (ref "Q12") (pin "5") (pinfunction "D_5") (pintype "passive"))
      (node (ref "Q12") (pin "6") (pinfunction "D_6") (pintype "passive"))
      (node (ref "Q12") (pin "7") (pinfunction "D_7") (pintype "passive"))
      (node (ref "Q12") (pin "8") (pinfunction "D_8") (pintype "passive"))
      (node (ref "R24") (pin "1") (pinfunction "1_1") (pintype "passive"))
      (node (ref "U7") (pin "6") (pinfunction "VS_6") (pintype "power_in"))
      (node (ref "X5") (pin "3") (pinfunction "3_3") (pintype "passive"))
    )
    (net (code "69") (name "W_IN-1CH") (class "Default")
      (node (ref "IC1") (pin "10") (pinfunction "PD6(AIN0)_10") (pintype "bidirectional"))
      (node (ref "U3") (pin "2") (pinfunction "IN_2") (pintype "input"))
    )
    (net (code "70") (name "W_IN-2CH") (class "Default")
      (node (ref "IC2") (pin "10") (pinfunction "PD6(AIN0)_10") (pintype "bidirectional"))
      (node (ref "U7") (pin "2") (pinfunction "IN_2") (pintype "input"))
    )
    (net (code "71") (name "W_SD-1CH") (class "Default")
      (node (ref "IC1") (pin "12") (pinfunction "PB0(ICP)_12") (pintype "bidirectional"))
      (node (ref "U3") (pin "3") (pinfunction "~{SD}_3") (pintype "input"))
    )
    (net (code "72") (name "W_SD-2CH") (class "Default")
      (node (ref "IC2") (pin "12") (pinfunction "PB0(ICP)_12") (pintype "bidirectional"))
      (node (ref "U7") (pin "3") (pinfunction "~{SD}_3") (pintype "input"))
    )
    (net (code "73") (name "unconnected-(IC1-ADC6-Pad19)") (class "Default")
      (node (ref "IC1") (pin "19") (pinfunction "ADC6_19") (pintype "bidirectional"))
    )
    (net (code "74") (name "unconnected-(IC1-ADC7-Pad22)") (class "Default")
      (node (ref "IC1") (pin "22") (pinfunction "ADC7_22") (pintype "bidirectional"))
    )
    (net (code "75") (name "unconnected-(IC1-PB1(OC1A)-Pad13)") (class "Default")
      (node (ref "IC1") (pin "13") (pinfunction "PB1(OC1A)_13") (pintype "bidirectional"))
    )
    (net (code "76") (name "unconnected-(IC1-PC4(ADC4{slash}SDA)-Pad27)") (class "Default")
      (node (ref "IC1") (pin "27") (pinfunction "PC4(ADC4/SDA)_27") (pintype "bidirectional"))
    )
    (net (code "77") (name "unconnected-(IC1-PC5(ADC5{slash}SCL)-Pad28)") (class "Default")
      (node (ref "IC1") (pin "28") (pinfunction "PC5(ADC5/SCL)_28") (pintype "bidirectional"))
    )
    (net (code "78") (name "unconnected-(IC1-PD1(TXD)-Pad31)") (class "Default")
      (node (ref "IC1") (pin "31") (pinfunction "PD1(TXD)_31") (pintype "bidirectional"))
    )
    (net (code "79") (name "unconnected-(IC1-PD2(INT0)-Pad32)") (class "Default")
      (node (ref "IC1") (pin "32") (pinfunction "PD2(INT0)_32") (pintype "bidirectional"))
    )
    (net (code "80") (name "unconnected-(IC2-ADC6-Pad19)") (class "Default")
      (node (ref "IC2") (pin "19") (pinfunction "ADC6_19") (pintype "bidirectional"))
    )
    (net (code "81") (name "unconnected-(IC2-ADC7-Pad22)") (class "Default")
      (node (ref "IC2") (pin "22") (pinfunction "ADC7_22") (pintype "bidirectional"))
    )
    (net (code "82") (name "unconnected-(IC2-PB1(OC1A)-Pad13)") (class "Default")
      (node (ref "IC2") (pin "13") (pinfunction "PB1(OC1A)_13") (pintype "bidirectional"))
    )
    (net (code "83") (name "unconnected-(IC2-PC4(ADC4{slash}SDA)-Pad27)") (class "Default")
      (node (ref "IC2") (pin "27") (pinfunction "PC4(ADC4/SDA)_27") (pintype "bidirectional"))
    )
    (net (code "84") (name "unconnected-(IC2-PC5(ADC5{slash}SCL)-Pad28)") (class "Default")
      (node (ref "IC2") (pin "28") (pinfunction "PC5(ADC5/SCL)_28") (pintype "bidirectional"))
    )
    (net (code "85") (name "unconnected-(IC2-PD1(TXD)-Pad31)") (class "Default")
      (node (ref "IC2") (pin "31") (pinfunction "PD1(TXD)_31") (pintype "bidirectional"))
    )
    (net (code "86") (name "unconnected-(IC2-PD2(INT0)-Pad32)") (class "Default")
      (node (ref "IC2") (pin "32") (pinfunction "PD2(INT0)_32") (pintype "bidirectional"))
    )
    (net (code "87") (name "~{RESET1}") (class "Default")
      (node (ref "IC1") (pin "29") (pinfunction "PC6(/RESET)_29") (pintype "bidirectional"))
      (node (ref "JP1") (pin "5") (pinfunction "5_5") (pintype "passive"))
      (node (ref "R14") (pin "2") (pinfunction "2_2") (pintype "passive"))
    )
    (net (code "88") (name "~{RESET2}") (class "Default")
      (node (ref "IC2") (pin "29") (pinfunction "PC6(/RESET)_29") (pintype "bidirectional"))
      (node (ref "JP2") (pin "5") (pinfunction "5_5") (pintype "passive"))
      (node (ref "R28") (pin "2") (pinfunction "2_2") (pintype "passive"))
    )
  )
)
